# gp5.net
KiCad netlist of a schematic drawn in EAGLE
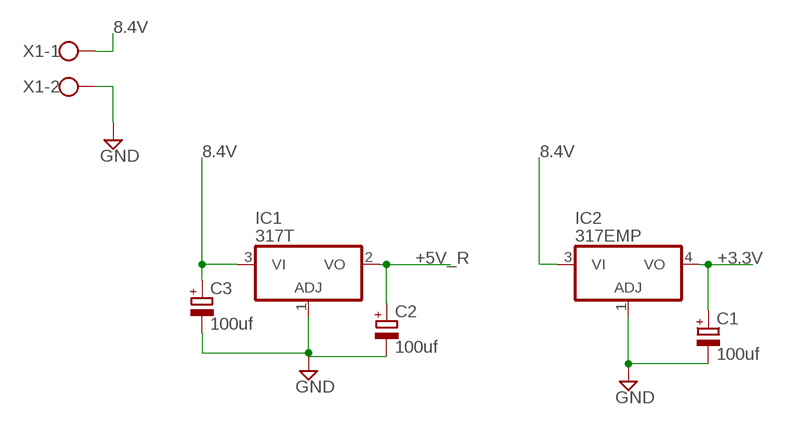
[diagram p0: schematic, sheet 1]
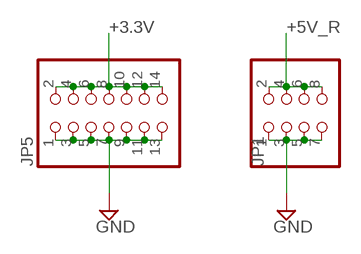
[diagram p1: schematic, sheet 2]

(export (version "E")
  (design (tool "Eeschema 10.0.6"))
  (components
    (comp (ref "C1")
      (value "100uf")
      (footprint "eagle-import:B45181B")
      (libsource (lib "eagle-import") (part "CPOL-EUB45181B"))
    )
    (comp (ref "C2")
      (value "100uf")
      (footprint "eagle-import:B45181B")
      (libsource (lib "eagle-import") (part "CPOL-EUB45181B"))
    )
    (comp (ref "C3")
      (value "100uf")
      (footprint "eagle-import:B45181B")
      (libsource (lib "eagle-import") (part "CPOL-EUB45181B"))
    )
    (comp (ref "IC1")
      (value "317T")
      (footprint "eagle-import:TO220H")
      (libsource (lib "eagle-import") (part "317T"))
    )
    (comp (ref "IC2")
      (value "317EMP")
      (footprint "eagle-import:SOT223")
      (libsource (lib "eagle-import") (part "317EMP"))
    )
    (comp (ref "X1")
      (value "W237-102")
      (footprint "eagle-import:W237-102")
      (fields (field (name "MPN") "237-102"))
      (libsource (lib "eagle-import") (part "W237-102"))
    )
    (comp (ref "JP1")
      (value "PINHD-2X4")
      (footprint "eagle-import:2X04")
      (libsource (lib "eagle-import") (part "PINHD-2X4"))
    )
    (comp (ref "JP5")
      (value "PINHD-2X7")
      (footprint "eagle-import:2X07")
      (libsource (lib "eagle-import") (part "PINHD-2X7"))
    )
  )
  (nets
    (net (code "1") (name "+3.3V") (class "Default")
      (node (ref "C1") (pin "+") (pinfunction "+_+") (pintype "passive"))
      (node (ref "IC2") (pin "4") (pinfunction "VO_4") (pintype "passive"))
      (node (ref "JP5") (pin "10") (pinfunction "10_10") (pintype "passive"))
      (node (ref "JP5") (pin "12") (pinfunction "12_12") (pintype "passive"))
      (node (ref "JP5") (pin "14") (pinfunction "14_14") (pintype "passive"))
      (node (ref "JP5") (pin "2") (pinfunction "2_2") (pintype "passive"))
      (node (ref "JP5") (pin "4") (pinfunction "4_4") (pintype "passive"))
      (node (ref "JP5") (pin "6") (pinfunction "6_6") (pintype "passive"))
      (node (ref "JP5") (pin "8") (pinfunction "8_8") (pintype "passive"))
    )
    (net (code "2") (name "+5V_R") (class "Default")
      (node (ref "C2") (pin "+") (pinfunction "+_+") (pintype "passive"))
      (node (ref "IC1") (pin "2") (pinfunction "VO_2") (pintype "passive"))
      (node (ref "JP1") (pin "2") (pinfunction "2_2") (pintype "passive"))
      (node (ref "JP1") (pin "4") (pinfunction "4_4") (pintype "passive"))
      (node (ref "JP1") (pin "6") (pinfunction "6_6") (pintype "passive"))
      (node (ref "JP1") (pin "8") (pinfunction "8_8") (pintype "passive"))
    )
    (net (code "3") (name "8.4V") (class "Default")
      (node (ref "C3") (pin "+") (pinfunction "+_+") (pintype "passive"))
      (node (ref "IC1") (pin "3") (pinfunction "VI_3") (pintype "input"))
      (node (ref "IC2") (pin "3") (pinfunction "VI_3") (pintype "input"))
      (node (ref "X1") (pin "1") (pinfunction "KL_1") (pintype "passive"))
    )
    (net (code "4") (name "GND") (class "Default")
      (node (ref "C1") (pin "-") (pinfunction "-_-") (pintype "passive"))
      (node (ref "C2") (pin "-") (pinfunction "-_-") (pintype "passive"))
      (node (ref "C3") (pin "-") (pinfunction "-_-") (pintype "passive"))
      (node (ref "IC1") (pin "1") (pinfunction "ADJ_1") (pintype "input"))
      (node (ref "IC2") (pin "1") (pinfunction "ADJ_1") (pintype "input"))
      (node (ref "JP1") (pin "1") (pinfunction "1_1") (pintype "passive"))
      (node (ref "JP1") (pin "3") (pinfunction "3_3") (pintype "passive"))
      (node (ref "JP1") (pin "5") (pinfunction "5_5") (pintype "passive"))
      (node (ref "JP1") (pin "7") (pinfunction "7_7") (pintype "passive"))
      (node (ref "JP5") (pin "1") (pinfunction "1_1") (pintype "passive"))
      (node (ref "JP5") (pin "11") (pinfunction "11_11") (pintype "passive"))
      (node (ref "JP5") (pin "13") (pinfunction "13_13") (pintype "passive"))
      (node (ref "JP5") (pin "3") (pinfunction "3_3") (pintype "passive"))
      (node (ref "JP5") (pin "5") (pinfunction "5_5") (pintype "passive"))
      (node (ref "JP5") (pin "7") (pinfunction "7_7") (pintype "passive"))
      (node (ref "JP5") (pin "9") (pinfunction "9_9") (pintype "passive"))
      (node (ref "X1") (pin "2") (pinfunction "KL_2") (pintype "passive"))
    )
  )
)
